# ZED-F9T.net
KiCad netlist of a schematic drawn in Altium Designer
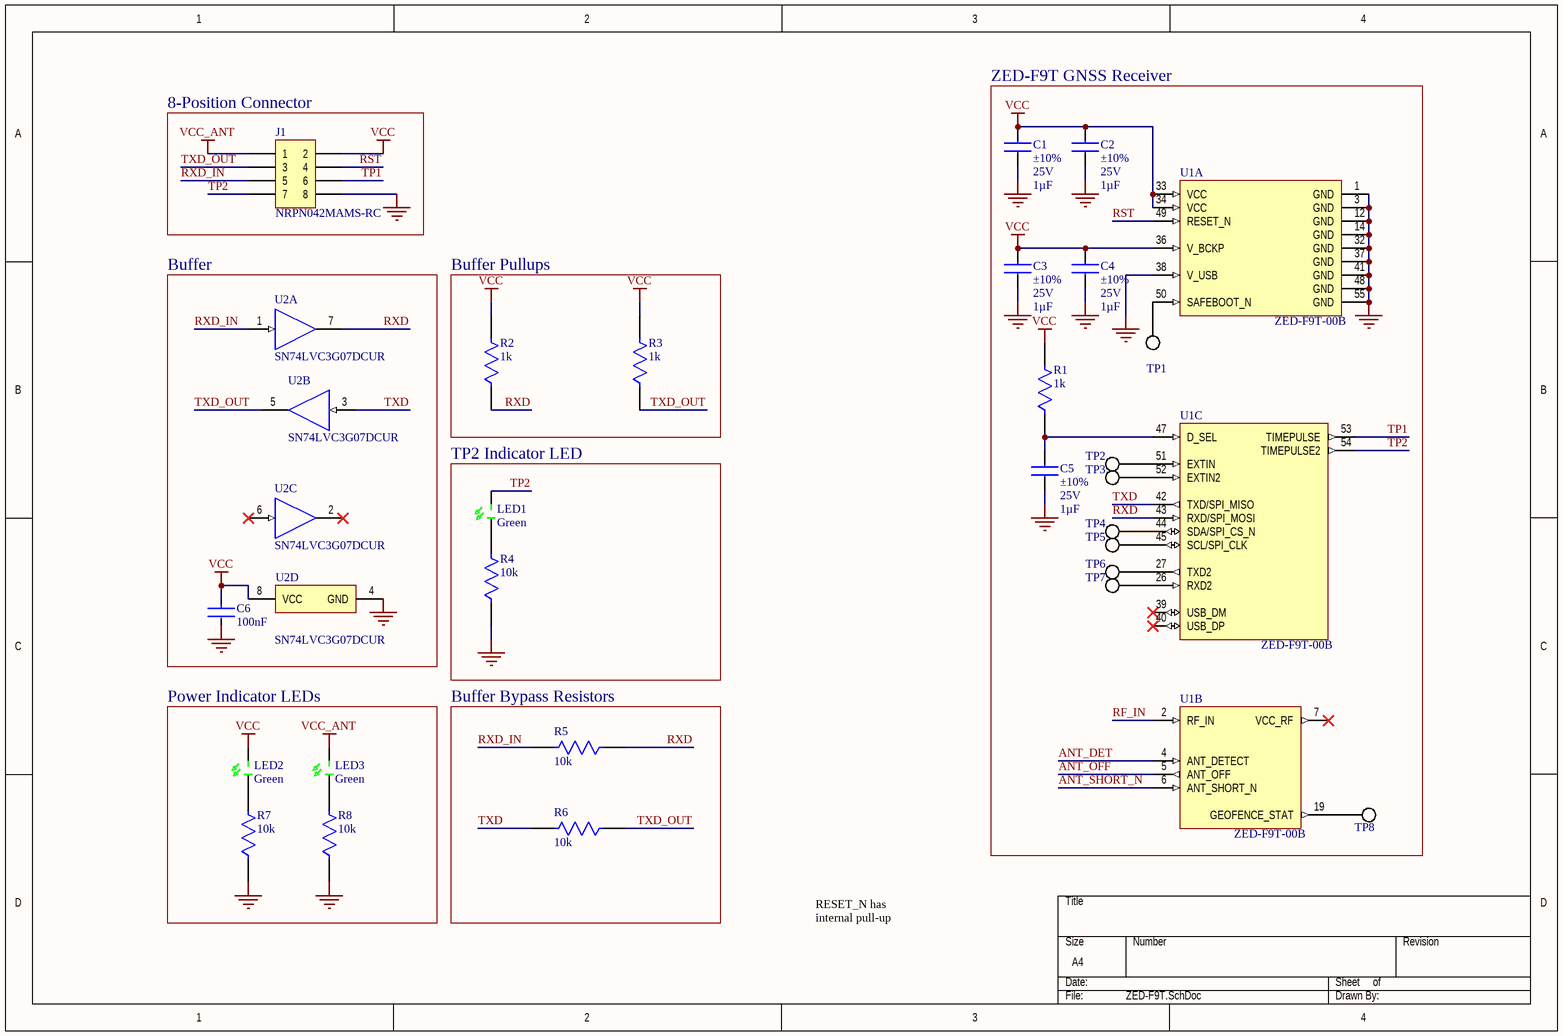
[diagram p0: ZED-F9T.SchDoc]

(export (version "E")
  (design (tool "Eeschema 10.0.6"))
  (components
    (comp (ref "C1")
      (value "Murata_GRM155R61E105KA12D")
      (footprint "CAPC1005X055N")
      (description "CAP, CER, X5R, 1UF, 10%, 25V, 0402, 0.55MM T")
      (fields
        (field (name "MANUFACTURER PART NUMBER") "GRM155R61E105KA12D")
        (field (name "TOLERANCE") "±10%")
        (field (name "VOLTAGE RATING") "25V")
        (field (name "MANUFACTURER") "Murata")
        (field (name "CAPACITANCE") "1µF")
      )
      (libsource (lib "RL Research Altium Server") (part "Capacitor_300mil"))
    )
    (comp (ref "C2")
      (value "Murata_GRM155R61E105KA12D")
      (footprint "CAPC1005X055N")
      (description "CAP, CER, X5R, 1UF, 10%, 25V, 0402, 0.55MM T")
      (fields
        (field (name "MANUFACTURER PART NUMBER") "GRM155R61E105KA12D")
        (field (name "TOLERANCE") "±10%")
        (field (name "VOLTAGE RATING") "25V")
        (field (name "MANUFACTURER") "Murata")
        (field (name "CAPACITANCE") "1µF")
      )
      (libsource (lib "RL Research Altium Server") (part "Capacitor_300mil"))
    )
    (comp (ref "C3")
      (value "Murata_GRM155R61E105KA12D")
      (footprint "CAPC1005X055N")
      (description "CAP, CER, X5R, 1UF, 10%, 25V, 0402, 0.55MM T")
      (fields
        (field (name "MANUFACTURER PART NUMBER") "GRM155R61E105KA12D")
        (field (name "TOLERANCE") "±10%")
        (field (name "VOLTAGE RATING") "25V")
        (field (name "MANUFACTURER") "Murata")
        (field (name "CAPACITANCE") "1µF")
      )
      (libsource (lib "RL Research Altium Server") (part "Capacitor_300mil"))
    )
    (comp (ref "C4")
      (value "Murata_GRM155R61E105KA12D")
      (footprint "CAPC1005X055N")
      (description "CAP, CER, X5R, 1UF, 10%, 25V, 0402, 0.55MM T")
      (fields
        (field (name "MANUFACTURER PART NUMBER") "GRM155R61E105KA12D")
        (field (name "TOLERANCE") "±10%")
        (field (name "VOLTAGE RATING") "25V")
        (field (name "MANUFACTURER") "Murata")
        (field (name "CAPACITANCE") "1µF")
      )
      (libsource (lib "RL Research Altium Server") (part "Capacitor_300mil"))
    )
    (comp (ref "C5")
      (value "Murata_GRM155R61E105KA12D")
      (footprint "CAPC1005X055N")
      (description "CAP, CER, X5R, 1UF, 10%, 25V, 0402, 0.55MM T")
      (fields
        (field (name "MANUFACTURER PART NUMBER") "GRM155R61E105KA12D")
        (field (name "TOLERANCE") "±10%")
        (field (name "VOLTAGE RATING") "25V")
        (field (name "MANUFACTURER") "Murata")
        (field (name "CAPACITANCE") "1µF")
      )
      (libsource (lib "RL Research Altium Server") (part "Capacitor_300mil"))
    )
    (comp (ref "C6")
      (value "100nF")
      (footprint "FP-0402-L_1_0_0_05-W_0_5-IPC_B")
      (description "None")
      (fields (field (name "TOLERANCE") "10%"))
      (libsource (lib "Altium Content Vault") (part "b4654b650e69147ec39a6b967a45e02"))
    )
    (comp (ref "J1")
      (value "NRPN042MAMS-RC")
      (footprint "NRPN042MAMS-RC")
      (description "Dual Row 8 Position 2 mm Pitch Surface Mount Header")
      (fields (field (name "MANUFACTURER") "Sullins"))
      (libsource (lib "GNSS_Receiver_Library") (part "NRPN042MAMS-RC"))
    )
    (comp (ref "LED1")
      (value "Lumex_SML-LXFM0603SUGCTR")
      (footprint "LEDS160X80X110-2N_LXFM0603-GR")
      (description "LED, GREEN, 574NM, 20MA, 20MCD MIN, 2.5VF MAX, 0603, 1.10MM T")
      (fields
        (field (name "INTERNAL PART NUMBER") "838-00422-00")
        (field (name "MANUFACTURER") "Lumex Opto/Components Inc.")
        (field (name "COLOR") "Green")
      )
      (libsource (lib "RL Research Altium Server") (part "LED_Green_300mil"))
    )
    (comp (ref "LED2")
      (value "Lumex_SML-LXFM0603SUGCTR")
      (footprint "LEDS160X80X110-2N_LXFM0603-GR")
      (description "LED, GREEN, 574NM, 20MA, 20MCD MIN, 2.5VF MAX, 0603, 1.10MM T")
      (fields
        (field (name "INTERNAL PART NUMBER") "838-00422-00")
        (field (name "MANUFACTURER") "Lumex Opto/Components Inc.")
        (field (name "COLOR") "Green")
      )
      (libsource (lib "RL Research Altium Server") (part "LED_Green_300mil"))
    )
    (comp (ref "LED3")
      (value "Lumex_SML-LXFM0603SUGCTR")
      (footprint "LEDS160X80X110-2N_LXFM0603-GR")
      (description "LED, GREEN, 574NM, 20MA, 20MCD MIN, 2.5VF MAX, 0603, 1.10MM T")
      (fields
        (field (name "INTERNAL PART NUMBER") "838-00422-00")
        (field (name "MANUFACTURER") "Lumex Opto/Components Inc.")
        (field (name "COLOR") "Green")
      )
      (libsource (lib "RL Research Altium Server") (part "LED_Green_300mil"))
    )
    (comp (ref "R1")
      (value "1k")
      (footprint "FP-RMCF0402-MFG")
      (description "1kΩ ±1% 0.063W 0402 Thick Film Chip Resistor AEC-Q200 compliant")
      (fields (field (name "TOLERANCE") "1%"))
      (libsource (lib "Altium Content Vault") (part "1029c3af85768c4190bb7ad29bc67b5"))
    )
    (comp (ref "R2")
      (value "1k")
      (footprint "FP-RMCF0402-MFG")
      (description "1kΩ ±1% 0.063W 0402 Thick Film Chip Resistor AEC-Q200 compliant")
      (fields (field (name "TOLERANCE") "1%"))
      (libsource (lib "Altium Content Vault") (part "1029c3af85768c4190bb7ad29bc67b5"))
    )
    (comp (ref "R3")
      (value "1k")
      (footprint "FP-RMCF0402-MFG")
      (description "1kΩ ±1% 0.063W 0402 Thick Film Chip Resistor AEC-Q200 compliant")
      (fields (field (name "TOLERANCE") "1%"))
      (libsource (lib "Altium Content Vault") (part "1029c3af85768c4190bb7ad29bc67b5"))
    )
    (comp (ref "R4")
      (value "10k")
      (footprint "FP-RMCF0402-IPC_C")
      (description "10kΩ ±1% 0.063W 0402 Thick Film Chip Resistor AEC-Q200 compliant")
      (fields (field (name "TOLERANCE") "1%"))
      (libsource (lib "Altium Content Vault") (part "1029c3af85768c4190bb7ad29bc67b5"))
    )
    (comp (ref "R5")
      (value "10k")
      (footprint "FP-RMCF0402-IPC_C")
      (description "10kΩ ±1% 0.063W 0402 Thick Film Chip Resistor AEC-Q200 compliant")
      (fields (field (name "TOLERANCE") "1%"))
      (libsource (lib "Altium Content Vault") (part "1029c3af85768c4190bb7ad29bc67b5"))
    )
    (comp (ref "R6")
      (value "10k")
      (footprint "FP-RMCF0402-IPC_C")
      (description "10kΩ ±1% 0.063W 0402 Thick Film Chip Resistor AEC-Q200 compliant")
      (fields (field (name "TOLERANCE") "1%"))
      (libsource (lib "Altium Content Vault") (part "1029c3af85768c4190bb7ad29bc67b5"))
    )
    (comp (ref "R7")
      (value "10k")
      (footprint "FP-RMCF0402-IPC_C")
      (description "10kΩ ±1% 0.063W 0402 Thick Film Chip Resistor AEC-Q200 compliant")
      (fields (field (name "TOLERANCE") "1%"))
      (libsource (lib "Altium Content Vault") (part "1029c3af85768c4190bb7ad29bc67b5"))
    )
    (comp (ref "R8")
      (value "10k")
      (footprint "FP-RMCF0402-IPC_C")
      (description "10kΩ ±1% 0.063W 0402 Thick Film Chip Resistor AEC-Q200 compliant")
      (fields (field (name "TOLERANCE") "1%"))
      (libsource (lib "Altium Content Vault") (part "1029c3af85768c4190bb7ad29bc67b5"))
    )
    (comp (ref "TP1")
      (value "SMT_100DIA")
      (footprint "TP001V_SMT_100DIA")
      (description "TEST POINT, PC, SMT, 1.00MM DIA")
      (libsource (lib "RL Research Altium Server") (part "TP_NoColor_001pin_No_BOM"))
    )
    (comp (ref "TP2")
      (value "SMT_100DIA")
      (footprint "TP001V_SMT_100DIA")
      (description "TEST POINT, PC, SMT, 1.00MM DIA")
      (libsource (lib "RL Research Altium Server") (part "TP_NoColor_001pin_No_BOM"))
    )
    (comp (ref "TP3")
      (value "SMT_100DIA")
      (footprint "TP001V_SMT_100DIA")
      (description "TEST POINT, PC, SMT, 1.00MM DIA")
      (libsource (lib "RL Research Altium Server") (part "TP_NoColor_001pin_No_BOM"))
    )
    (comp (ref "TP4")
      (value "SMT_100DIA")
      (footprint "TP001V_SMT_100DIA")
      (description "TEST POINT, PC, SMT, 1.00MM DIA")
      (libsource (lib "RL Research Altium Server") (part "TP_NoColor_001pin_No_BOM"))
    )
    (comp (ref "TP5")
      (value "SMT_100DIA")
      (footprint "TP001V_SMT_100DIA")
      (description "TEST POINT, PC, SMT, 1.00MM DIA")
      (libsource (lib "RL Research Altium Server") (part "TP_NoColor_001pin_No_BOM"))
    )
    (comp (ref "TP6")
      (value "SMT_100DIA")
      (footprint "TP001V_SMT_100DIA")
      (description "TEST POINT, PC, SMT, 1.00MM DIA")
      (libsource (lib "RL Research Altium Server") (part "TP_NoColor_001pin_No_BOM"))
    )
    (comp (ref "TP7")
      (value "SMT_100DIA")
      (footprint "TP001V_SMT_100DIA")
      (description "TEST POINT, PC, SMT, 1.00MM DIA")
      (libsource (lib "RL Research Altium Server") (part "TP_NoColor_001pin_No_BOM"))
    )
    (comp (ref "TP8")
      (value "SMT_100DIA")
      (footprint "TP001V_SMT_100DIA")
      (description "TEST POINT, PC, SMT, 1.00MM DIA")
      (libsource (lib "RL Research Altium Server") (part "TP_NoColor_001pin_No_BOM"))
    )
    (comp (ref "U1")
      (value "ZED-F9T-00B")
      (footprint "GPS_ZED-F9T")
      (description "Multi-band GNSS Receiver with Nanosecond-level Timing Accuracy")
      (fields (field (name "MANUFACTURER") "u-blox"))
      (libsource (lib "GNSS_Receiver_Library") (part "GPS_ZED-F9T"))
    )
    (comp (ref "U2")
      (value "SN74LVC3G07DCUR")
      (footprint "DCU0008A_N")
      (description "Triple Buffer/Driver With Open-Drain Output, DCU0008A, LARGE T&R")
      (fields
        (field (name "GENERIC PART NUMBER") "SN74LVC3G07")
        (field (name "MANUFACTURER") "Texas Instruments")
      )
      (libsource (lib "Altium Content Vault") (part "TI-SN74XXX3G0X-XX-8"))
    )
  )
  (nets
    (net (code "1") (name "/ANT_DET") (class "Default")
      (node (ref "U1") (pin "4") (pinfunction "ANT_DETECT_4") (pintype "input"))
    )
    (net (code "2") (name "/ANT_OFF") (class "Default")
      (node (ref "U1") (pin "5") (pinfunction "ANT_OFF_5") (pintype "output"))
    )
    (net (code "3") (name "/ANT_SHORT_N") (class "Default")
      (node (ref "U1") (pin "6") (pinfunction "ANT_SHORT_N_6") (pintype "input"))
    )
    (net (code "4") (name "/RF_IN") (class "Default")
      (node (ref "U1") (pin "2") (pinfunction "RF_IN_2") (pintype "input"))
    )
    (net (code "5") (name "/RST") (class "Default")
      (node (ref "J1") (pin "4") (pinfunction "4_4") (pintype "passive"))
      (node (ref "U1") (pin "49") (pinfunction "RESET_N_49") (pintype "input"))
    )
    (net (code "6") (name "/RXD") (class "Default")
      (node (ref "R2") (pin "1") (pinfunction "1_1") (pintype "passive"))
      (node (ref "R5") (pin "1") (pinfunction "1_1") (pintype "passive"))
      (node (ref "U1") (pin "43") (pinfunction "RXD/SPI_MOSI_43") (pintype "input"))
      (node (ref "U2") (pin "7") (pinfunction "1Y_7") (pintype "open_collector"))
    )
    (net (code "7") (name "/RXD_IN") (class "Default")
      (node (ref "J1") (pin "5") (pinfunction "5_5") (pintype "passive"))
      (node (ref "R5") (pin "2") (pinfunction "2_2") (pintype "passive"))
      (node (ref "U2") (pin "1") (pinfunction "1A_1") (pintype "input"))
    )
    (net (code "8") (name "/TP1") (class "Default")
      (node (ref "J1") (pin "6") (pinfunction "6_6") (pintype "passive"))
      (node (ref "U1") (pin "53") (pinfunction "TIMEPULSE_53") (pintype "output"))
    )
    (net (code "9") (name "/TP2") (class "Default")
      (node (ref "J1") (pin "7") (pinfunction "7_7") (pintype "passive"))
      (node (ref "LED1") (pin "A") (pinfunction "Anode_A") (pintype "passive"))
      (node (ref "U1") (pin "54") (pinfunction "TIMEPULSE2_54") (pintype "output"))
    )
    (net (code "10") (name "/TXD") (class "Default")
      (node (ref "R6") (pin "2") (pinfunction "2_2") (pintype "passive"))
      (node (ref "U1") (pin "42") (pinfunction "TXD/SPI_MISO_42") (pintype "output"))
      (node (ref "U2") (pin "3") (pinfunction "2A_3") (pintype "input"))
    )
    (net (code "11") (name "/TXD_OUT") (class "Default")
      (node (ref "J1") (pin "3") (pinfunction "3_3") (pintype "passive"))
      (node (ref "R3") (pin "1") (pinfunction "1_1") (pintype "passive"))
      (node (ref "R6") (pin "1") (pinfunction "1_1") (pintype "passive"))
      (node (ref "U2") (pin "5") (pinfunction "2Y_5") (pintype "open_collector"))
    )
    (net (code "12") (name "GND") (class "Default")
      (node (ref "C1") (pin "2") (pinfunction "2_2") (pintype "passive"))
      (node (ref "C2") (pin "2") (pinfunction "2_2") (pintype "passive"))
      (node (ref "C3") (pin "2") (pinfunction "2_2") (pintype "passive"))
      (node (ref "C4") (pin "2") (pinfunction "2_2") (pintype "passive"))
      (node (ref "C5") (pin "2") (pinfunction "2_2") (pintype "passive"))
      (node (ref "C6") (pin "2") (pinfunction "2_2") (pintype "passive"))
      (node (ref "J1") (pin "8") (pinfunction "8_8") (pintype "passive"))
      (node (ref "R4") (pin "1") (pinfunction "1_1") (pintype "passive"))
      (node (ref "R7") (pin "1") (pinfunction "1_1") (pintype "passive"))
      (node (ref "R8") (pin "1") (pinfunction "1_1") (pintype "passive"))
      (node (ref "U1") (pin "1") (pinfunction "GND_1") (pintype "passive"))
      (node (ref "U1") (pin "12") (pinfunction "GND_12") (pintype "passive"))
      (node (ref "U1") (pin "14") (pinfunction "GND_14") (pintype "passive"))
      (node (ref "U1") (pin "3") (pinfunction "GND_3") (pintype "passive"))
      (node (ref "U1") (pin "32") (pinfunction "GND_32") (pintype "passive"))
      (node (ref "U1") (pin "37") (pinfunction "GND_37") (pintype "passive"))
      (node (ref "U1") (pin "38") (pinfunction "V_USB_38") (pintype "input"))
      (node (ref "U1") (pin "41") (pinfunction "GND_41") (pintype "passive"))
      (node (ref "U1") (pin "48") (pinfunction "GND_48") (pintype "passive"))
      (node (ref "U1") (pin "55") (pinfunction "GND_55") (pintype "passive"))
      (node (ref "U2") (pin "4") (pinfunction "GND_4") (pintype "power_in"))
    )
    (net (code "13") (name "Net-(LED1-Cathode)") (class "Default")
      (node (ref "LED1") (pin "K") (pinfunction "Cathode_K") (pintype "passive"))
      (node (ref "R4") (pin "2") (pinfunction "2_2") (pintype "passive"))
    )
    (net (code "14") (name "Net-(LED2-Cathode)") (class "Default")
      (node (ref "LED2") (pin "K") (pinfunction "Cathode_K") (pintype "passive"))
      (node (ref "R7") (pin "2") (pinfunction "2_2") (pintype "passive"))
    )
    (net (code "15") (name "Net-(LED3-Cathode)") (class "Default")
      (node (ref "LED3") (pin "K") (pinfunction "Cathode_K") (pintype "passive"))
      (node (ref "R8") (pin "2") (pinfunction "2_2") (pintype "passive"))
    )
    (net (code "16") (name "Net-(U1A-SAFEBOOT_N)") (class "Default")
      (node (ref "TP1") (pin "1") (pinfunction "1_1") (pintype "passive"))
      (node (ref "U1") (pin "50") (pinfunction "SAFEBOOT_N_50") (pintype "input"))
    )
    (net (code "17") (name "Net-(U1B-GEOFENCE_STAT)") (class "Default")
      (node (ref "TP8") (pin "1") (pinfunction "1_1") (pintype "passive"))
      (node (ref "U1") (pin "19") (pinfunction "GEOFENCE_STAT_19") (pintype "output"))
    )
    (net (code "18") (name "Net-(U1C-D_SEL)") (class "Default")
      (node (ref "C5") (pin "1") (pinfunction "1_1") (pintype "passive"))
      (node (ref "R1") (pin "1") (pinfunction "1_1") (pintype "passive"))
      (node (ref "U1") (pin "47") (pinfunction "D_SEL_47") (pintype "input"))
    )
    (net (code "19") (name "Net-(U1C-EXTIN)") (class "Default")
      (node (ref "TP2") (pin "1") (pinfunction "1_1") (pintype "passive"))
      (node (ref "U1") (pin "51") (pinfunction "EXTIN_51") (pintype "input"))
    )
    (net (code "20") (name "Net-(U1C-EXTIN2)") (class "Default")
      (node (ref "TP3") (pin "1") (pinfunction "1_1") (pintype "passive"))
      (node (ref "U1") (pin "52") (pinfunction "EXTIN2_52") (pintype "input"))
    )
    (net (code "21") (name "Net-(U1C-RXD2)") (class "Default")
      (node (ref "TP7") (pin "1") (pinfunction "1_1") (pintype "passive"))
      (node (ref "U1") (pin "26") (pinfunction "RXD2_26") (pintype "input"))
    )
    (net (code "22") (name "Net-(U1C-SCL{slash}SPI_CLK)") (class "Default")
      (node (ref "TP5") (pin "1") (pinfunction "1_1") (pintype "passive"))
      (node (ref "U1") (pin "45") (pinfunction "SCL/SPI_CLK_45") (pintype "bidirectional"))
    )
    (net (code "23") (name "Net-(U1C-SDA{slash}SPI_CS_N)") (class "Default")
      (node (ref "TP4") (pin "1") (pinfunction "1_1") (pintype "passive"))
      (node (ref "U1") (pin "44") (pinfunction "SDA/SPI_CS_N_44") (pintype "bidirectional"))
    )
    (net (code "24") (name "Net-(U1C-TXD2)") (class "Default")
      (node (ref "TP6") (pin "1") (pinfunction "1_1") (pintype "passive"))
      (node (ref "U1") (pin "27") (pinfunction "TXD2_27") (pintype "output"))
    )
    (net (code "25") (name "VCC") (class "Default")
      (node (ref "C1") (pin "1") (pinfunction "1_1") (pintype "passive"))
      (node (ref "C2") (pin "1") (pinfunction "1_1") (pintype "passive"))
      (node (ref "C3") (pin "1") (pinfunction "1_1") (pintype "passive"))
      (node (ref "C4") (pin "1") (pinfunction "1_1") (pintype "passive"))
      (node (ref "C6") (pin "1") (pinfunction "1_1") (pintype "passive"))
      (node (ref "J1") (pin "2") (pinfunction "2_2") (pintype "passive"))
      (node (ref "LED2") (pin "A") (pinfunction "Anode_A") (pintype "passive"))
      (node (ref "R1") (pin "2") (pinfunction "2_2") (pintype "passive"))
      (node (ref "R2") (pin "2") (pinfunction "2_2") (pintype "passive"))
      (node (ref "R3") (pin "2") (pinfunction "2_2") (pintype "passive"))
      (node (ref "U1") (pin "33") (pinfunction "VCC_33") (pintype "input"))
      (node (ref "U1") (pin "34") (pinfunction "VCC_34") (pintype "input"))
      (node (ref "U1") (pin "36") (pinfunction "V_BCKP_36") (pintype "input"))
      (node (ref "U2") (pin "8") (pinfunction "VCC_8") (pintype "power_in"))
    )
    (net (code "26") (name "VCC_ANT") (class "Default")
      (node (ref "J1") (pin "1") (pinfunction "1_1") (pintype "passive"))
      (node (ref "LED3") (pin "A") (pinfunction "Anode_A") (pintype "passive"))
    )
    (net (code "27") (name "unconnected-(U1B-VCC_RF-Pad7)") (class "Default")
      (node (ref "U1") (pin "7") (pinfunction "VCC_RF_7") (pintype "output+no_connect"))
    )
    (net (code "28") (name "unconnected-(U1C-USB_DM-Pad39)") (class "Default")
      (node (ref "U1") (pin "39") (pinfunction "USB_DM_39") (pintype "bidirectional+no_connect"))
    )
    (net (code "29") (name "unconnected-(U1C-USB_DP-Pad40)") (class "Default")
      (node (ref "U1") (pin "40") (pinfunction "USB_DP_40") (pintype "bidirectional+no_connect"))
    )
    (net (code "30") (name "unconnected-(U2C-3A-Pad6)") (class "Default")
      (node (ref "U2") (pin "6") (pinfunction "3A_6") (pintype "input+no_connect"))
    )
    (net (code "31") (name "unconnected-(U2C-3Y-Pad2)") (class "Default")
      (node (ref "U2") (pin "2") (pinfunction "3Y_2") (pintype "open_collector+no_connect"))
    )
  )
)
